# Badge_TAV.net
KiCad netlist of a schematic drawn in Altium Designer
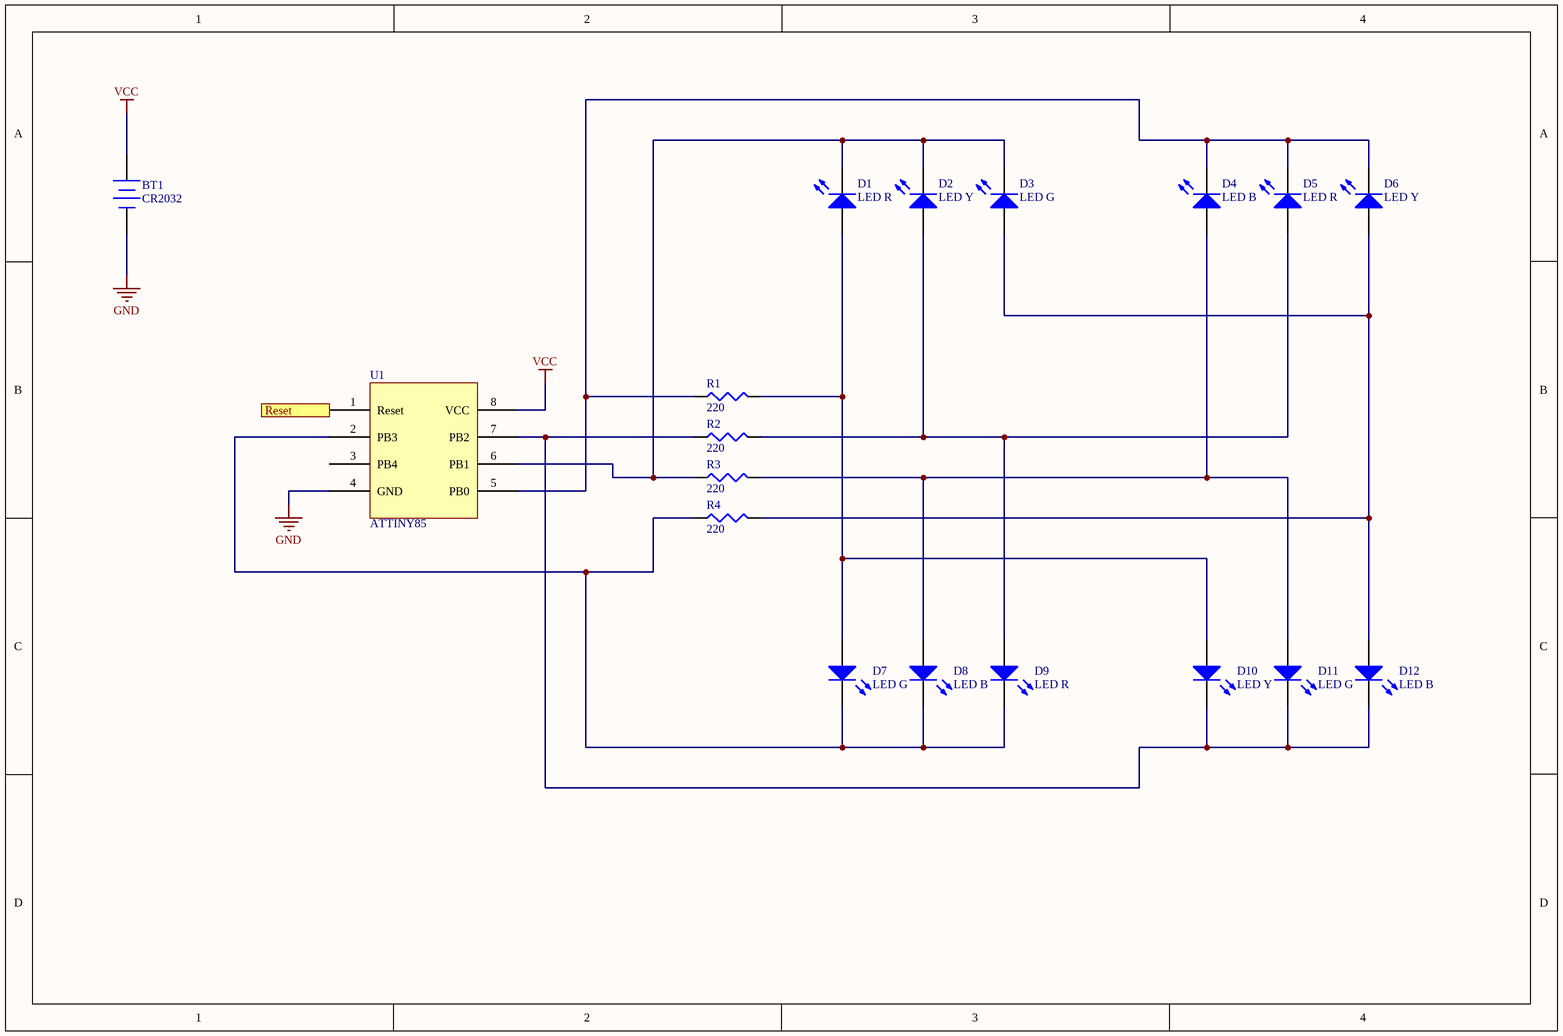
[diagram p0: Badge TAV.SchDoc]

(export (version "E")
  (design (tool "Eeschema 10.0.6"))
  (components
    (comp (ref "BT1")
      (value "CR2032")
      (footprint "CR2032")
      (description "Multicell Battery")
      (libsource (lib "Miscellaneous Devices") (part "Battery"))
    )
    (comp (ref "D1")
      (value "LED R")
      (footprint "LED 3.5mm - Sense Símbol")
      (libsource (lib "Miscellaneous Devices") (part "LED0"))
    )
    (comp (ref "D2")
      (value "LED Y")
      (footprint "LED 3.5mm - Sense Símbol")
      (libsource (lib "Miscellaneous Devices") (part "LED0"))
    )
    (comp (ref "D3")
      (value "LED G")
      (footprint "LED 3.5mm - Sense Símbol")
      (libsource (lib "Miscellaneous Devices") (part "LED0"))
    )
    (comp (ref "D4")
      (value "LED B")
      (footprint "LED 3.5mm - Sense Símbol")
      (libsource (lib "Miscellaneous Devices") (part "LED0"))
    )
    (comp (ref "D5")
      (value "LED R")
      (footprint "LED 3.5mm - Sense Símbol")
      (libsource (lib "Miscellaneous Devices") (part "LED0"))
    )
    (comp (ref "D6")
      (value "LED Y")
      (footprint "LED 3.5mm - Sense Símbol")
      (libsource (lib "Miscellaneous Devices") (part "LED0"))
    )
    (comp (ref "D7")
      (value "LED G")
      (footprint "LED 3.5mm - Sense Símbol")
      (libsource (lib "Miscellaneous Devices") (part "LED0"))
    )
    (comp (ref "D8")
      (value "LED B")
      (footprint "LED 3.5mm - Sense Símbol")
      (libsource (lib "Miscellaneous Devices") (part "LED0"))
    )
    (comp (ref "D9")
      (value "LED R")
      (footprint "LED 3.5mm - Sense Símbol")
      (libsource (lib "Miscellaneous Devices") (part "LED0"))
    )
    (comp (ref "D10")
      (value "LED Y")
      (footprint "LED 3.5mm - Sense Símbol")
      (libsource (lib "Miscellaneous Devices") (part "LED0"))
    )
    (comp (ref "D11")
      (value "LED G")
      (footprint "LED 3.5mm - Sense Símbol")
      (libsource (lib "Miscellaneous Devices") (part "LED0"))
    )
    (comp (ref "D12")
      (value "LED B")
      (footprint "LED 3.5mm - Sense Símbol")
      (libsource (lib "Miscellaneous Devices") (part "LED0"))
    )
    (comp (ref "R1")
      (value "220")
      (footprint "AXIAL-0.4")
      (description "Resistor")
      (libsource (lib "Miscellaneous Devices") (part "Res3"))
    )
    (comp (ref "R2")
      (value "220")
      (footprint "AXIAL-0.4")
      (description "Resistor")
      (libsource (lib "Miscellaneous Devices") (part "Res3"))
    )
    (comp (ref "R3")
      (value "220")
      (footprint "AXIAL-0.4")
      (description "Resistor")
      (libsource (lib "Miscellaneous Devices") (part "Res3"))
    )
    (comp (ref "R4")
      (value "220")
      (footprint "AXIAL-0.4")
      (description "Resistor")
      (libsource (lib "Miscellaneous Devices") (part "Res3"))
    )
    (comp (ref "U1")
      (value "ATTINY85")
      (footprint "DIP8")
      (libsource (lib "Llibreries Altium Lluis") (part "ATTINY85"))
    )
  )
  (nets
    (net (code "1") (name "/Reset") (class "Default")
      (node (ref "U1") (pin "1") (pinfunction "Reset_1") (pintype "passive"))
    )
    (net (code "2") (name "GND") (class "Default")
      (node (ref "BT1") (pin "2") (pinfunction "-_2") (pintype "passive"))
      (node (ref "U1") (pin "4") (pinfunction "GND_4") (pintype "passive"))
    )
    (net (code "3") (name "Net-(D1-A)") (class "Default")
      (node (ref "D1") (pin "1") (pinfunction "A_1") (pintype "passive"))
      (node (ref "D10") (pin "1") (pinfunction "A_1") (pintype "passive"))
      (node (ref "D7") (pin "1") (pinfunction "A_1") (pintype "passive"))
      (node (ref "R1") (pin "2") (pinfunction "2_2") (pintype "passive"))
    )
    (net (code "4") (name "Net-(D1-K)") (class "Default")
      (node (ref "D1") (pin "2") (pinfunction "K_2") (pintype "passive"))
      (node (ref "D2") (pin "2") (pinfunction "K_2") (pintype "passive"))
      (node (ref "D3") (pin "2") (pinfunction "K_2") (pintype "passive"))
      (node (ref "R3") (pin "1") (pinfunction "1_1") (pintype "passive"))
      (node (ref "U1") (pin "6") (pinfunction "PB1_6") (pintype "passive"))
    )
    (net (code "5") (name "Net-(D2-A)") (class "Default")
      (node (ref "D2") (pin "1") (pinfunction "A_1") (pintype "passive"))
      (node (ref "D5") (pin "1") (pinfunction "A_1") (pintype "passive"))
      (node (ref "D9") (pin "1") (pinfunction "A_1") (pintype "passive"))
      (node (ref "R2") (pin "2") (pinfunction "2_2") (pintype "passive"))
    )
    (net (code "6") (name "Net-(D4-K)") (class "Default")
      (node (ref "D4") (pin "2") (pinfunction "K_2") (pintype "passive"))
      (node (ref "D5") (pin "2") (pinfunction "K_2") (pintype "passive"))
      (node (ref "D6") (pin "2") (pinfunction "K_2") (pintype "passive"))
      (node (ref "R1") (pin "1") (pinfunction "1_1") (pintype "passive"))
      (node (ref "U1") (pin "5") (pinfunction "PB0_5") (pintype "passive"))
    )
    (net (code "7") (name "Net-(D7-K)") (class "Default")
      (node (ref "D7") (pin "2") (pinfunction "K_2") (pintype "passive"))
      (node (ref "D8") (pin "2") (pinfunction "K_2") (pintype "passive"))
      (node (ref "D9") (pin "2") (pinfunction "K_2") (pintype "passive"))
      (node (ref "R4") (pin "1") (pinfunction "1_1") (pintype "passive"))
      (node (ref "U1") (pin "2") (pinfunction "PB3_2") (pintype "passive"))
    )
    (net (code "8") (name "Net-(D10-K)") (class "Default")
      (node (ref "D10") (pin "2") (pinfunction "K_2") (pintype "passive"))
      (node (ref "D11") (pin "2") (pinfunction "K_2") (pintype "passive"))
      (node (ref "D12") (pin "2") (pinfunction "K_2") (pintype "passive"))
      (node (ref "R2") (pin "1") (pinfunction "1_1") (pintype "passive"))
      (node (ref "U1") (pin "7") (pinfunction "PB2_7") (pintype "passive"))
    )
    (net (code "9") (name "Net-(D11-A)") (class "Default")
      (node (ref "D11") (pin "1") (pinfunction "A_1") (pintype "passive"))
      (node (ref "D4") (pin "1") (pinfunction "A_1") (pintype "passive"))
      (node (ref "D8") (pin "1") (pinfunction "A_1") (pintype "passive"))
      (node (ref "R3") (pin "2") (pinfunction "2_2") (pintype "passive"))
    )
    (net (code "10") (name "Net-(D12-A)") (class "Default")
      (node (ref "D12") (pin "1") (pinfunction "A_1") (pintype "passive"))
      (node (ref "D3") (pin "1") (pinfunction "A_1") (pintype "passive"))
      (node (ref "D6") (pin "1") (pinfunction "A_1") (pintype "passive"))
      (node (ref "R4") (pin "2") (pinfunction "2_2") (pintype "passive"))
    )
    (net (code "11") (name "VCC") (class "Default")
      (node (ref "BT1") (pin "1") (pinfunction "+_1") (pintype "passive"))
      (node (ref "U1") (pin "8") (pinfunction "VCC_8") (pintype "passive"))
    )
    (net (code "12") (name "unconnected-(U1-PB4-Pad3)") (class "Default")
      (node (ref "U1") (pin "3") (pinfunction "PB4_3") (pintype "passive"))
    )
  )
)
